# Tiny817_Xplained_Pro_current_measurement.net
KiCad netlist of a schematic drawn in Altium Designer
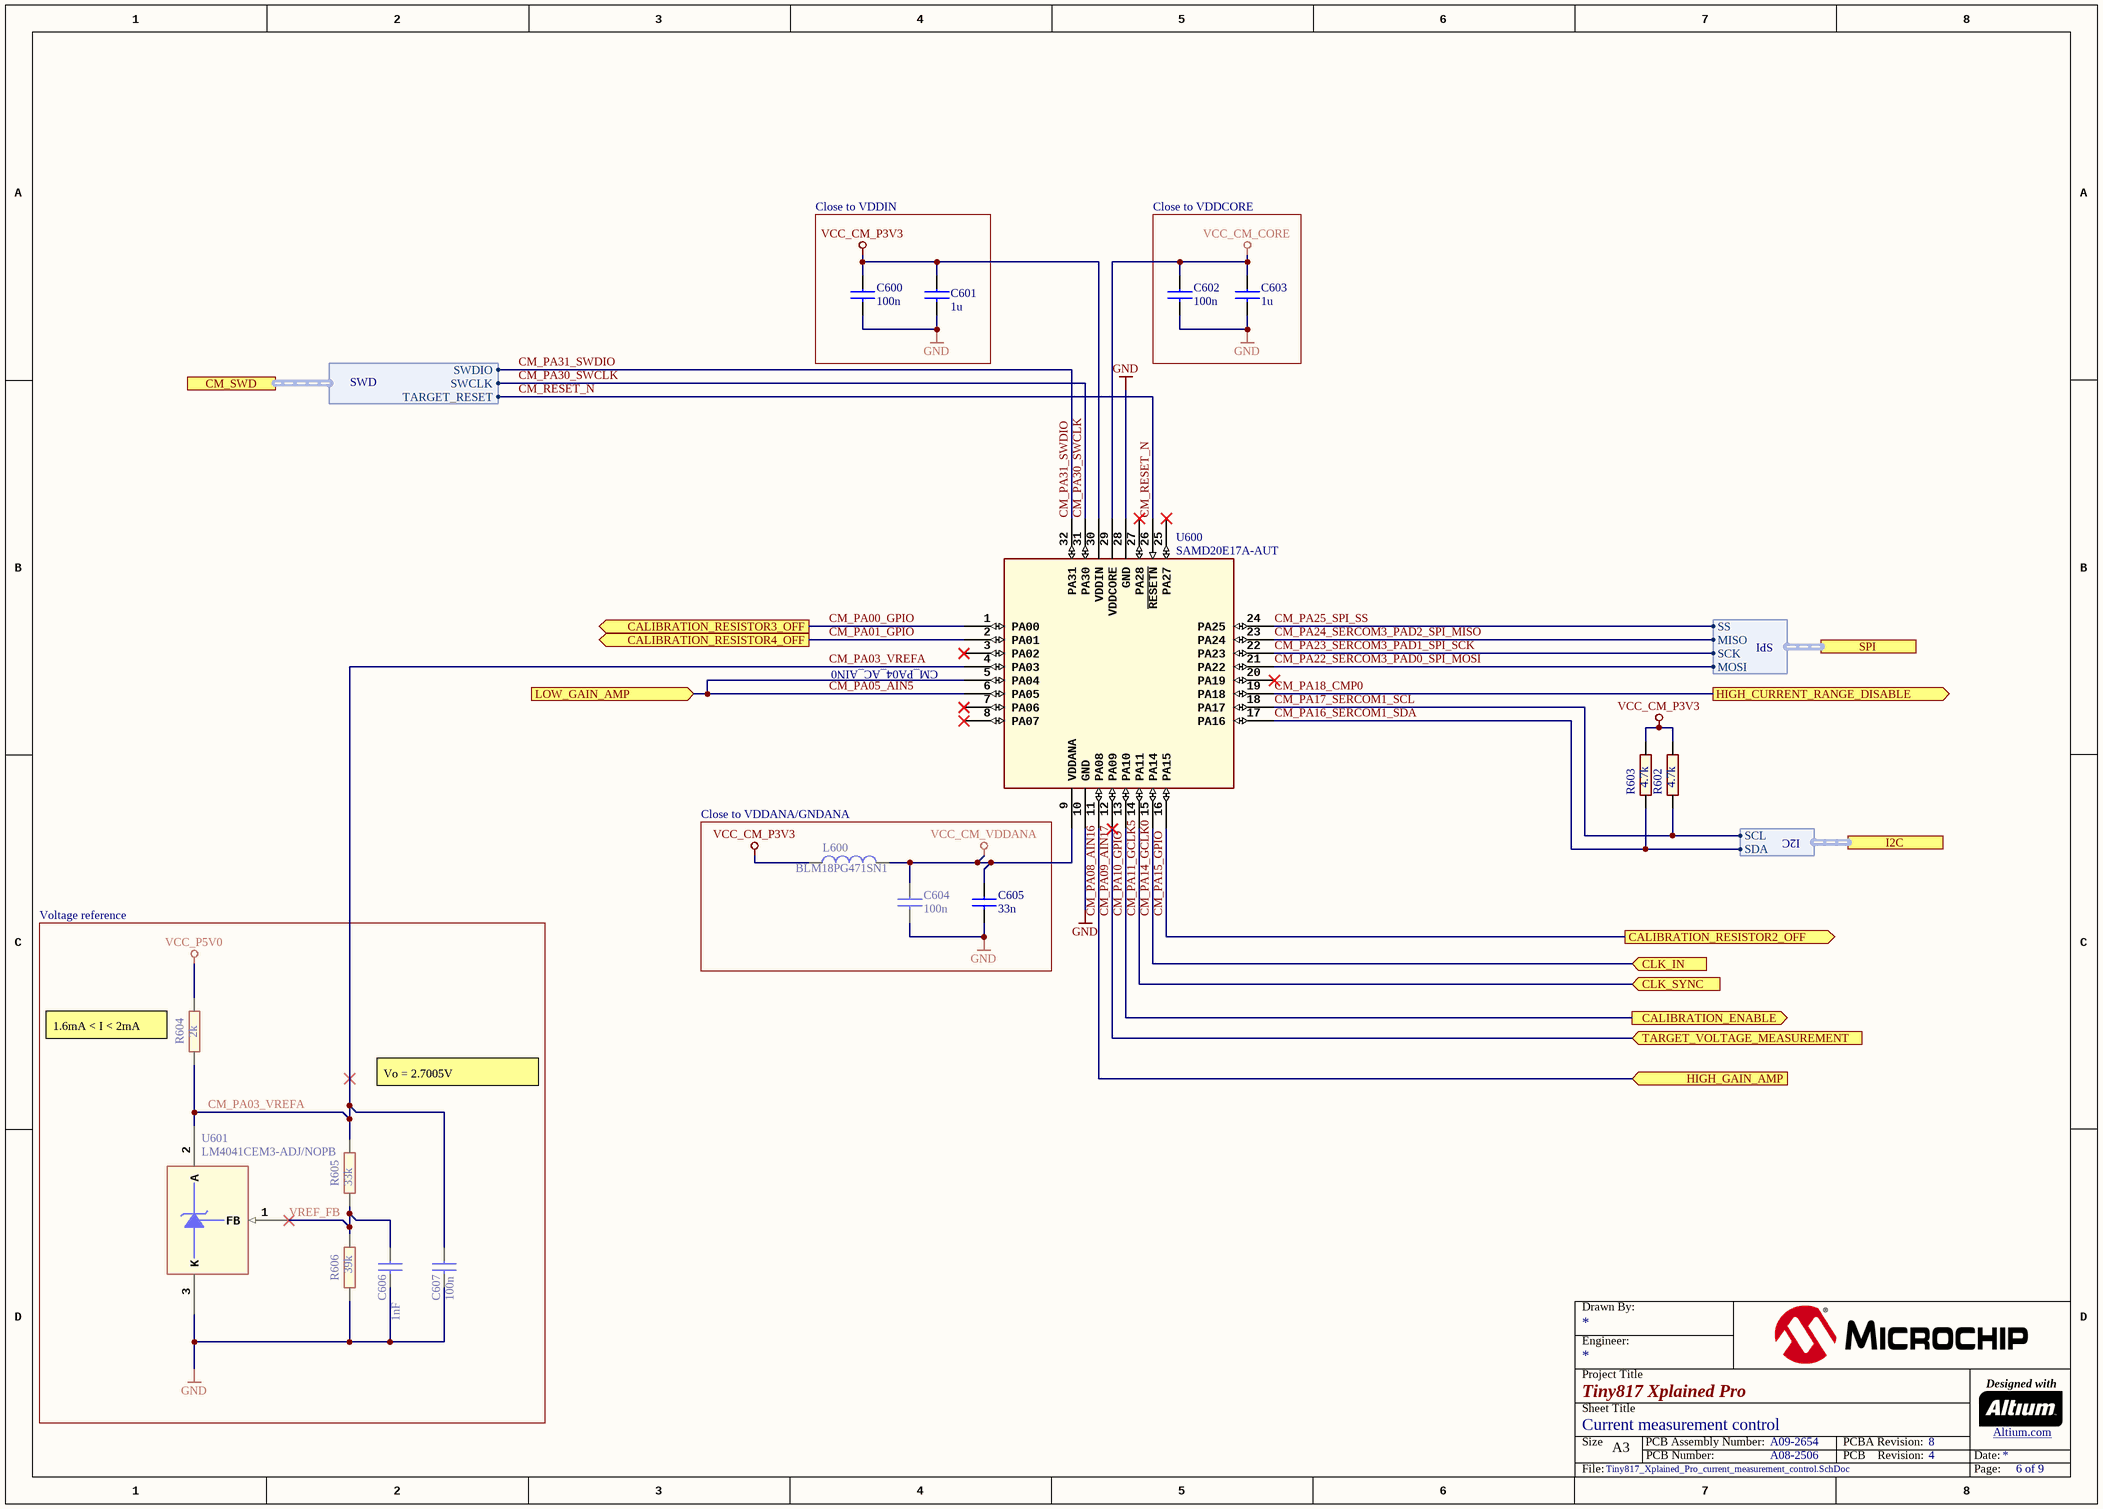
[diagram p0: Tiny817_Xplained_Pro_current_measurement_control.SchDoc]

(export (version "E")
  (design (tool "Eeschema 10.0.6"))
  (components
    (comp (ref "C600")
      (value "100n")
      (footprint "AP1-00053")
      (description "Ceramic capacitor, SMD 0402, X7R, 16V, +/-10%")
      (fields (field (name "TOLERANCE") "16V, +/-10%") (field (name "MANUFACTURER") "Kemet"))
      (libsource (lib "AltiumDbLib") (part "CAP-NONPOL"))
    )
    (comp (ref "C601")
      (value "1u")
      (footprint "AP1-00001")
      (description "Ceramic capacitor, SMD 0402, X5R, 6.3V, +/-10% (de26942)")
      (fields (field (name "TOLERANCE") "+/-10%") (field (name "MANUFACTURER") "Kemet"))
      (libsource (lib "AltiumDbLib") (part "CAP-NONPOL"))
    )
    (comp (ref "C602")
      (value "100n")
      (footprint "AP1-00053")
      (description "Ceramic capacitor, SMD 0402, X7R, 16V, +/-10%")
      (fields (field (name "TOLERANCE") "16V, +/-10%") (field (name "MANUFACTURER") "Kemet"))
      (libsource (lib "AltiumDbLib") (part "CAP-NONPOL"))
    )
    (comp (ref "C603")
      (value "1u")
      (footprint "AP1-00001")
      (description "Ceramic capacitor, SMD 0402, X5R, 6.3V, +/-10% (de26942)")
      (fields (field (name "TOLERANCE") "+/-10%") (field (name "MANUFACTURER") "Kemet"))
      (libsource (lib "AltiumDbLib") (part "CAP-NONPOL"))
    )
    (comp (ref "C604")
      (value "100n")
      (footprint "AP1-00053")
      (description "Ceramic capacitor, SMD 0402, X7R, 16V, +/-10%")
      (fields (field (name "TOLERANCE") "16V, +/-10%") (field (name "MANUFACTURER") "Kemet"))
      (libsource (lib "AltiumDbLib") (part "CAP-NONPOL"))
    )
    (comp (ref "C605")
      (value "33n")
      (footprint "AP1-00053")
      (description "Ceramic capacitor, SMD 0402, X7R, 25V, ±10%")
      (fields (field (name "TOLERANCE") "±10%(K)") (field (name "MANUFACTURER") "Murata"))
      (libsource (lib "AltiumDbLib") (part "CAP-NONPOL"))
    )
    (comp (ref "C606")
      (value "1nF")
      (footprint "AP1-00053")
      (description "Ceramic capacitor, SMD 0402, C0G, 50V, +/-5%")
      (fields (field (name "TOLERANCE") "5%") (field (name "MANUFACTURER") "Murata"))
      (libsource (lib "AltiumDbLib") (part "CAP-NONPOL"))
    )
    (comp (ref "C607")
      (value "100n")
      (footprint "AP1-00053")
      (description "Ceramic capacitor, SMD 0402, X7R, 16V, +/-10%")
      (fields (field (name "TOLERANCE") "16V, +/-10%") (field (name "MANUFACTURER") "Kemet"))
      (libsource (lib "AltiumDbLib") (part "CAP-NONPOL"))
    )
    (comp (ref "L600")
      (value "BLM18PG471SN1")
      (footprint "AP3-00005")
      (description "SMD RF inductor 0603. Z=470Ohm (@100MHz), Max R(dc)=0.20Ohm, Max current=1A")
      (fields (field (name "MANUFACTURER") "Murata"))
      (libsource (lib "AltiumDbLib") (part "INDUCTOR"))
    )
    (comp (ref "R602")
      (value "4.7k")
      (footprint "AP2-00011")
      (description "Thick film resistor, SMD 0402, 1/16W, 1%")
      (fields (field (name "TOLERANCE") "1 %") (field (name "MANUFACTURER") "Panasonic"))
      (libsource (lib "") (part "R2_1"))
    )
    (comp (ref "R603")
      (value "4.7k")
      (footprint "AP2-00011")
      (description "Thick film resistor, SMD 0402, 1/16W, 1%")
      (fields (field (name "TOLERANCE") "1 %") (field (name "MANUFACTURER") "Panasonic"))
      (libsource (lib "") (part "R2_1"))
    )
    (comp (ref "R604")
      (value "2k")
      (footprint "AP2-00011")
      (description "Thick film resistor, SMD 0402, 1/16W, 1%")
      (fields (field (name "TOLERANCE") "1 %"))
      (libsource (lib "AltiumDbLib") (part "R2"))
    )
    (comp (ref "R605")
      (value "33k")
      (footprint "AP2-00011")
      (description "Thick film resistor, SMD 0402, 1/16W, 1%")
      (fields (field (name "TOLERANCE") "1 %") (field (name "MANUFACTURER") "ASJ Holdings"))
      (libsource (lib "AltiumDbLib") (part "R2"))
    )
    (comp (ref "R606")
      (value "39k")
      (footprint "AP2-00011")
      (description "Thick film resistor, SMD 0402, 1/16W, 1%")
      (fields (field (name "TOLERANCE") "1 %") (field (name "MANUFACTURER") "ASJ Holdings"))
      (libsource (lib "AltiumDbLib") (part "R2"))
    )
    (comp (ref "U600")
      (value "SAMD20E17A-AUT")
      (footprint "AP6-00061")
      (description "Atmel 32bit RISC MCU 32 pin")
      (fields (field (name "MANUFACTURER") "Microchip") (field (name "MPN") "ATSAMD20E17A-AUT"))
      (libsource (lib "AltiumDbLib") (part "SAMD20E"))
    )
    (comp (ref "U601")
      (value "LM4041CEM3-ADJ/NOPB")
      (footprint "AP5-00002")
      (description "Adjustable shunt voltage regulator, 1.24 to 10V out")
      (fields (field (name "MANUFACTURER") "Texas Instruments"))
      (libsource (lib "AltiumDbLib") (part "LM4041-ADJ"))
    )
  )
  (nets
    (net (code "4") (name "/CM_PA00_GPIO") (class "Default")
      (node (ref "U600") (pin "1") (pinfunction "PA00_1") (pintype "bidirectional"))
    )
    (net (code "5") (name "/CM_PA01_GPIO") (class "Default")
      (node (ref "U600") (pin "2") (pinfunction "PA01_2") (pintype "bidirectional"))
    )
    (net (code "6") (name "/CM_PA03_VREFA") (class "Default")
      (node (ref "C607") (pin "1") (pinfunction "1_1") (pintype "passive"))
      (node (ref "R604") (pin "1") (pinfunction "1_1") (pintype "passive"))
      (node (ref "R605") (pin "2") (pinfunction "2_2") (pintype "passive"))
      (node (ref "U600") (pin "4") (pinfunction "PA03_4") (pintype "bidirectional"))
      (node (ref "U601") (pin "2") (pinfunction "A_2") (pintype "power_in"))
    )
    (net (code "7") (name "/CM_PA05_AIN5") (class "Default")
      (node (ref "U600") (pin "5") (pinfunction "PA04_5") (pintype "bidirectional"))
      (node (ref "U600") (pin "6") (pinfunction "PA05_6") (pintype "bidirectional"))
    )
    (net (code "8") (name "/CM_PA08_AIN16") (class "Default")
      (node (ref "U600") (pin "11") (pinfunction "PA08_11") (pintype "bidirectional"))
    )
    (net (code "9") (name "/CM_PA09_AIN17") (class "Default")
      (node (ref "U600") (pin "12") (pinfunction "PA09_12") (pintype "bidirectional+no_connect"))
    )
    (net (code "10") (name "/CM_PA10_GPIO") (class "Default")
      (node (ref "U600") (pin "13") (pinfunction "PA10_13") (pintype "bidirectional"))
    )
    (net (code "11") (name "/CM_PA11_GCLK5") (class "Default")
      (node (ref "U600") (pin "14") (pinfunction "PA11_14") (pintype "bidirectional"))
    )
    (net (code "12") (name "/CM_PA14_GCLK0") (class "Default")
      (node (ref "U600") (pin "15") (pinfunction "PA14_15") (pintype "bidirectional"))
    )
    (net (code "13") (name "/CM_PA15_GPIO") (class "Default")
      (node (ref "U600") (pin "16") (pinfunction "PA15_16") (pintype "bidirectional"))
    )
    (net (code "14") (name "/CM_PA16_SERCOM1_SDA") (class "Default")
      (node (ref "R603") (pin "1") (pinfunction "1_1") (pintype "passive"))
      (node (ref "U600") (pin "17") (pinfunction "PA16_17") (pintype "bidirectional"))
    )
    (net (code "15") (name "/CM_PA17_SERCOM1_SCL") (class "Default")
      (node (ref "R602") (pin "1") (pinfunction "1_1") (pintype "passive"))
      (node (ref "U600") (pin "18") (pinfunction "PA17_18") (pintype "bidirectional"))
    )
    (net (code "16") (name "/CM_PA18_CMP0") (class "Default")
      (node (ref "U600") (pin "19") (pinfunction "PA18_19") (pintype "bidirectional"))
    )
    (net (code "17") (name "/CM_PA22_SERCOM3_PAD0_SPI_MOSI") (class "Default")
      (node (ref "U600") (pin "21") (pinfunction "PA22_21") (pintype "bidirectional"))
    )
    (net (code "18") (name "/CM_PA23_SERCOM3_PAD1_SPI_SCK") (class "Default")
      (node (ref "U600") (pin "22") (pinfunction "PA23_22") (pintype "bidirectional"))
    )
    (net (code "19") (name "/CM_PA24_SERCOM3_PAD2_SPI_MISO") (class "Default")
      (node (ref "U600") (pin "23") (pinfunction "PA24_23") (pintype "bidirectional"))
    )
    (net (code "20") (name "/CM_PA25_SPI_SS") (class "Default")
      (node (ref "U600") (pin "24") (pinfunction "PA25_24") (pintype "bidirectional"))
    )
    (net (code "21") (name "/CM_PA30_SWCLK") (class "Default")
      (node (ref "U600") (pin "31") (pinfunction "PA30_31") (pintype "bidirectional"))
    )
    (net (code "22") (name "/CM_PA31_SWDIO") (class "Default")
      (node (ref "U600") (pin "32") (pinfunction "PA31_32") (pintype "bidirectional"))
    )
    (net (code "23") (name "/CM_RESET_N") (class "Default")
      (node (ref "U600") (pin "26") (pinfunction "~{RESETN}_26") (pintype "input"))
    )
    (net (code "24") (name "/VREF_FB") (class "Default")
      (node (ref "C606") (pin "1") (pinfunction "1_1") (pintype "passive"))
      (node (ref "R605") (pin "1") (pinfunction "1_1") (pintype "passive"))
      (node (ref "R606") (pin "2") (pinfunction "2_2") (pintype "passive"))
      (node (ref "U601") (pin "1") (pinfunction "FB_1") (pintype "input"))
    )
    (net (code "28") (name "GND") (class "Default")
      (node (ref "C600") (pin "2") (pinfunction "2_2") (pintype "passive"))
      (node (ref "C601") (pin "2") (pinfunction "2_2") (pintype "passive"))
      (node (ref "C602") (pin "2") (pinfunction "2_2") (pintype "passive"))
      (node (ref "C603") (pin "2") (pinfunction "2_2") (pintype "passive"))
      (node (ref "C604") (pin "2") (pinfunction "2_2") (pintype "passive"))
      (node (ref "C605") (pin "2") (pinfunction "2_2") (pintype "passive"))
      (node (ref "C606") (pin "2") (pinfunction "2_2") (pintype "passive"))
      (node (ref "C607") (pin "2") (pinfunction "2_2") (pintype "passive"))
      (node (ref "R606") (pin "1") (pinfunction "1_1") (pintype "passive"))
      (node (ref "U600") (pin "10") (pinfunction "GND_10") (pintype "power_in"))
      (node (ref "U600") (pin "28") (pinfunction "GND_28") (pintype "power_in"))
      (node (ref "U601") (pin "3") (pinfunction "K_3") (pintype "power_in"))
    )
    (net (code "29") (name "VCC_CM_CORE") (class "Default")
      (node (ref "C602") (pin "1") (pinfunction "1_1") (pintype "passive"))
      (node (ref "C603") (pin "1") (pinfunction "1_1") (pintype "passive"))
      (node (ref "U600") (pin "29") (pinfunction "VDDCORE_29") (pintype "power_in"))
    )
    (net (code "30") (name "VCC_CM_P3V3") (class "Default")
      (node (ref "C600") (pin "1") (pinfunction "1_1") (pintype "passive"))
      (node (ref "C601") (pin "1") (pinfunction "1_1") (pintype "passive"))
      (node (ref "L600") (pin "1") (pinfunction "1_1") (pintype "passive"))
      (node (ref "R602") (pin "2") (pinfunction "2_2") (pintype "passive"))
      (node (ref "R603") (pin "2") (pinfunction "2_2") (pintype "passive"))
      (node (ref "U600") (pin "30") (pinfunction "VDDIN_30") (pintype "power_in"))
    )
    (net (code "31") (name "VCC_CM_VDDANA") (class "Default")
      (node (ref "C604") (pin "1") (pinfunction "1_1") (pintype "passive"))
      (node (ref "C605") (pin "1") (pinfunction "1_1") (pintype "passive"))
      (node (ref "L600") (pin "2") (pinfunction "2_2") (pintype "passive"))
      (node (ref "U600") (pin "9") (pinfunction "VDDANA_9") (pintype "power_in"))
    )
    (net (code "32") (name "VCC_P5V0") (class "Default")
      (node (ref "R604") (pin "2") (pinfunction "2_2") (pintype "passive"))
    )
    (net (code "33") (name "unconnected-(U600-PA02-Pad3)") (class "Default")
      (node (ref "U600") (pin "3") (pinfunction "PA02_3") (pintype "bidirectional+no_connect"))
    )
    (net (code "34") (name "unconnected-(U600-PA06-Pad7)") (class "Default")
      (node (ref "U600") (pin "7") (pinfunction "PA06_7") (pintype "bidirectional+no_connect"))
    )
    (net (code "35") (name "unconnected-(U600-PA07-Pad8)") (class "Default")
      (node (ref "U600") (pin "8") (pinfunction "PA07_8") (pintype "bidirectional+no_connect"))
    )
    (net (code "36") (name "unconnected-(U600-PA19-Pad20)") (class "Default")
      (node (ref "U600") (pin "20") (pinfunction "PA19_20") (pintype "bidirectional+no_connect"))
    )
    (net (code "37") (name "unconnected-(U600-PA27-Pad25)") (class "Default")
      (node (ref "U600") (pin "25") (pinfunction "PA27_25") (pintype "bidirectional+no_connect"))
    )
    (net (code "38") (name "unconnected-(U600-PA28-Pad27)") (class "Default")
      (node (ref "U600") (pin "27") (pinfunction "PA28_27") (pintype "bidirectional+no_connect"))
    )
  )
)
